# DrvPAPCNC.net
KiCad netlist of a schematic drawn in EAGLE
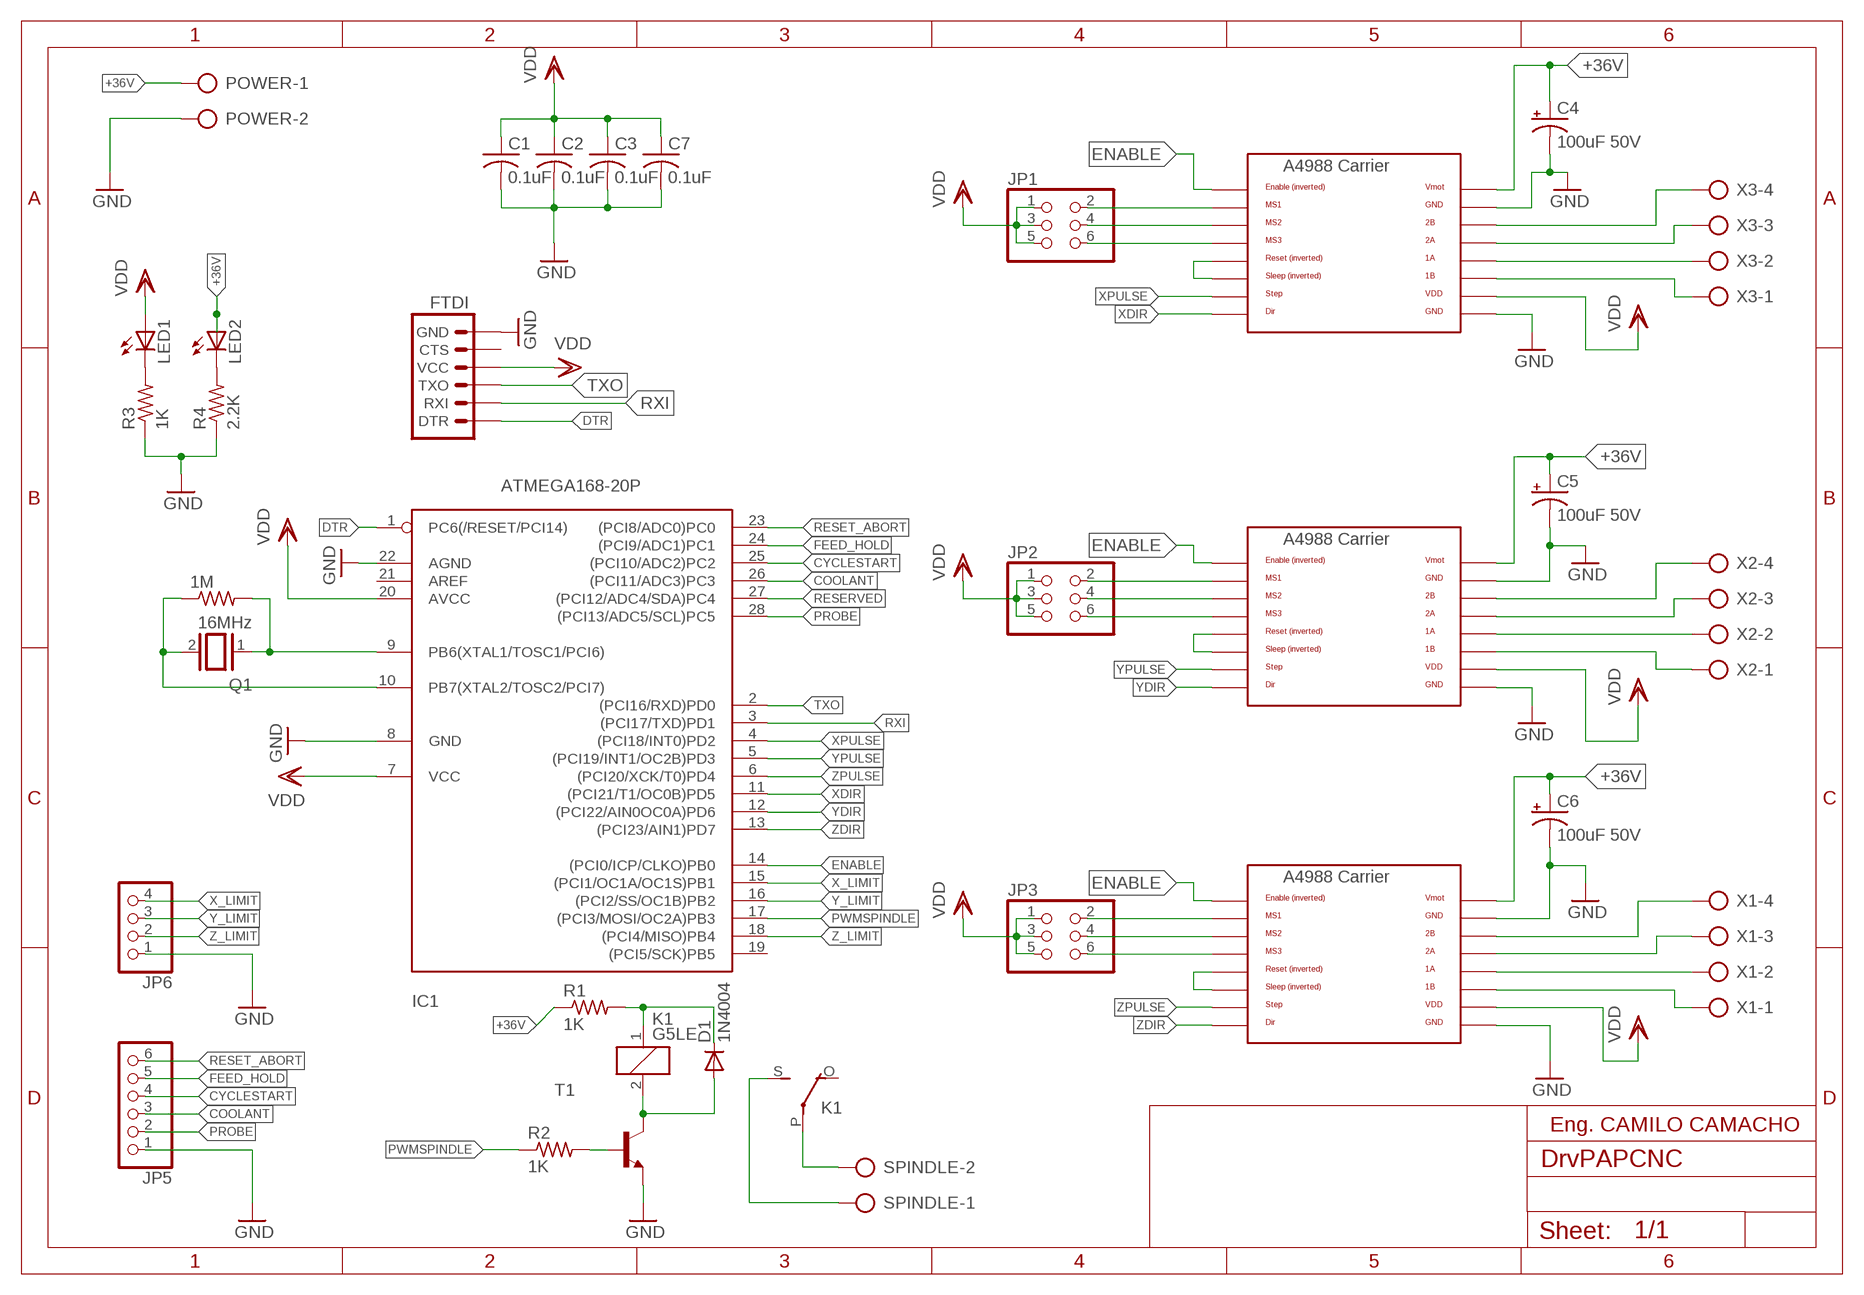
[diagram p0: schematic, sheet 1]

(export (version "E")
  (design (tool "Eeschema 10.0.6"))
  (components
    (comp (ref "1M")
      (value "R-US_0204/2V")
      (footprint "eagle-import:0204V")
      (libsource (lib "eagle-import") (part "R-US_0204/2V"))
    )
    (comp (ref "C1")
      (value "0.1uF")
      (footprint "eagle-import:C025-025X050")
      (libsource (lib "eagle-import") (part "C-US025-025X050"))
    )
    (comp (ref "C2")
      (value "0.1uF")
      (footprint "eagle-import:C025-025X050")
      (libsource (lib "eagle-import") (part "C-US025-025X050"))
    )
    (comp (ref "C3")
      (value "0.1uF")
      (footprint "eagle-import:C025-025X050")
      (libsource (lib "eagle-import") (part "C-US025-025X050"))
    )
    (comp (ref "C4")
      (value "100uF 50V")
      (footprint "eagle-import:E7,5-16")
      (libsource (lib "eagle-import") (part "CPOL-USE7.5-16"))
    )
    (comp (ref "C5")
      (value "100uF 50V")
      (footprint "eagle-import:E7,5-16")
      (libsource (lib "eagle-import") (part "CPOL-USE7.5-16"))
    )
    (comp (ref "C6")
      (value "100uF 50V")
      (footprint "eagle-import:E7,5-16")
      (libsource (lib "eagle-import") (part "CPOL-USE7.5-16"))
    )
    (comp (ref "C7")
      (value "0.1uF")
      (footprint "eagle-import:C025-025X050")
      (libsource (lib "eagle-import") (part "C-US025-025X050"))
    )
    (comp (ref "D1")
      (value "1N4004")
      (footprint "eagle-import:DO41-10")
      (libsource (lib "eagle-import") (part "1N4004"))
    )
    (comp (ref "FTDI")
      (value "ARDUINO_SERIAL_PROGRAMPTH")
      (footprint "eagle-import:1X06")
      (libsource (lib "eagle-import") (part "ARDUINO_SERIAL_PROGRAMPTH"))
    )
    (comp (ref "IC1")
      (value "ATMEGA168-20P")
      (footprint "eagle-import:DIL28-3")
      (libsource (lib "eagle-import") (part "ATMEGA168P-20"))
    )
    (comp (ref "JP1")
      (value "PINHD-2X3")
      (footprint "eagle-import:2X03")
      (libsource (lib "eagle-import") (part "PINHD-2X3"))
    )
    (comp (ref "JP2")
      (value "PINHD-2X3")
      (footprint "eagle-import:2X03")
      (libsource (lib "eagle-import") (part "PINHD-2X3"))
    )
    (comp (ref "JP3")
      (value "PINHD-2X3")
      (footprint "eagle-import:2X03")
      (libsource (lib "eagle-import") (part "PINHD-2X3"))
    )
    (comp (ref "JP5")
      (value "PINHD-1X6")
      (footprint "eagle-import:1X06")
      (libsource (lib "eagle-import") (part "PINHD-1X6"))
    )
    (comp (ref "JP6")
      (value "PINHD-1X4")
      (footprint "eagle-import:1X04")
      (libsource (lib "eagle-import") (part "PINHD-1X4"))
    )
    (comp (ref "K1")
      (value "G5LE")
      (footprint "eagle-import:G5LE")
      (libsource (lib "eagle-import") (part "G5LE"))
    )
    (comp (ref "LED1")
      (value "LED5MM")
      (footprint "eagle-import:LED5MM")
      (libsource (lib "eagle-import") (part "LED5MM"))
    )
    (comp (ref "LED2")
      (value "LED5MM")
      (footprint "eagle-import:LED5MM")
      (libsource (lib "eagle-import") (part "LED5MM"))
    )
    (comp (ref "POWER")
      (value "AK300/2")
      (footprint "eagle-import:AK300_2")
      (libsource (lib "eagle-import") (part "AK300/2"))
    )
    (comp (ref "Q1")
      (value "16MHz")
      (footprint "eagle-import:QS")
      (libsource (lib "eagle-import") (part "XTAL/S"))
    )
    (comp (ref "R1")
      (value "1K")
      (footprint "eagle-import:0207_10")
      (libsource (lib "eagle-import") (part "R-US_0207/10"))
    )
    (comp (ref "R2")
      (value "1K")
      (footprint "eagle-import:0207_10")
      (libsource (lib "eagle-import") (part "R-US_0207/10"))
    )
    (comp (ref "R3")
      (value "1K")
      (footprint "eagle-import:0207_10")
      (libsource (lib "eagle-import") (part "R-US_0207/10"))
    )
    (comp (ref "R4")
      (value "2.2K")
      (footprint "eagle-import:0207_10")
      (libsource (lib "eagle-import") (part "R-US_0207/10"))
    )
    (comp (ref "SPINDLE")
      (value "AK300/2")
      (footprint "eagle-import:AK300_2")
      (libsource (lib "eagle-import") (part "AK300/2"))
    )
    (comp (ref "T1")
      (value "2N3904-NPN-TO92-EBC")
      (footprint "eagle-import:TO92-EBC")
      (libsource (lib "eagle-import") (part "-NPN-TO92-EBC2N3904"))
    )
    (comp (ref "U$1")
      (value "A4988BREAKOUT")
      (footprint "eagle-import:A4988BREAKOUT")
      (libsource (lib "eagle-import") (part "A4988BREAKOUT"))
    )
    (comp (ref "U$2")
      (value "A4988BREAKOUT")
      (footprint "eagle-import:A4988BREAKOUT")
      (libsource (lib "eagle-import") (part "A4988BREAKOUT"))
    )
    (comp (ref "U$3")
      (value "A4988BREAKOUT")
      (footprint "eagle-import:A4988BREAKOUT")
      (libsource (lib "eagle-import") (part "A4988BREAKOUT"))
    )
    (comp (ref "X1")
      (value "AK300/4")
      (footprint "eagle-import:AK300_4")
      (libsource (lib "eagle-import") (part "AK300/4"))
    )
    (comp (ref "X2")
      (value "AK300/4")
      (footprint "eagle-import:AK300_4")
      (libsource (lib "eagle-import") (part "AK300/4"))
    )
    (comp (ref "X3")
      (value "AK300/4")
      (footprint "eagle-import:AK300_4")
      (libsource (lib "eagle-import") (part "AK300/4"))
    )
  )
  (nets
    (net (code "1") (name "+36V") (class "Default")
      (node (ref "C4") (pin "+") (pinfunction "+_+") (pintype "passive"))
      (node (ref "C5") (pin "+") (pinfunction "+_+") (pintype "passive"))
      (node (ref "C6") (pin "+") (pinfunction "+_+") (pintype "passive"))
      (node (ref "LED2") (pin "A") (pinfunction "A_A") (pintype "passive"))
      (node (ref "POWER") (pin "1") (pinfunction "KL_1") (pintype "passive"))
      (node (ref "R1") (pin "1") (pinfunction "1_1") (pintype "passive"))
      (node (ref "U$1") (pin "VMOT") (pinfunction "VMOT_VMOT") (pintype "power_in"))
      (node (ref "U$2") (pin "VMOT") (pinfunction "VMOT_VMOT") (pintype "power_in"))
      (node (ref "U$3") (pin "VMOT") (pinfunction "VMOT_VMOT") (pintype "power_in"))
    )
    (net (code "2") (name "COOLANT") (class "Default")
      (node (ref "IC1") (pin "26") (pinfunction "(PCI11/ADC3)PC3_26") (pintype "bidirectional"))
      (node (ref "JP5") (pin "3") (pinfunction "3_3") (pintype "passive"))
    )
    (net (code "3") (name "CYCLESTART") (class "Default")
      (node (ref "IC1") (pin "25") (pinfunction "(PCI10/ADC2)PC2_25") (pintype "bidirectional"))
      (node (ref "JP5") (pin "4") (pinfunction "4_4") (pintype "passive"))
    )
    (net (code "4") (name "DTR") (class "Default")
      (node (ref "FTDI") (pin "1") (pinfunction "DTR_1") (pintype "passive"))
      (node (ref "IC1") (pin "1") (pinfunction "PC6(/RESET/PCI14)_1") (pintype "bidirectional"))
    )
    (net (code "5") (name "ENABLE") (class "Default")
      (node (ref "IC1") (pin "14") (pinfunction "(PCI0/ICP/CLKO)PB0_14") (pintype "bidirectional"))
      (node (ref "U$1") (pin "EN") (pinfunction "EN_EN") (pintype "input"))
      (node (ref "U$2") (pin "EN") (pinfunction "EN_EN") (pintype "input"))
      (node (ref "U$3") (pin "EN") (pinfunction "EN_EN") (pintype "input"))
    )
    (net (code "6") (name "FEED_HOLD") (class "Default")
      (node (ref "IC1") (pin "24") (pinfunction "(PCI9/ADC1)PC1_24") (pintype "bidirectional"))
      (node (ref "JP5") (pin "5") (pinfunction "5_5") (pintype "passive"))
    )
    (net (code "7") (name "GND") (class "Default")
      (node (ref "C1") (pin "2") (pinfunction "2_2") (pintype "passive"))
      (node (ref "C2") (pin "2") (pinfunction "2_2") (pintype "passive"))
      (node (ref "C3") (pin "2") (pinfunction "2_2") (pintype "passive"))
      (node (ref "C4") (pin "-") (pinfunction "-_-") (pintype "passive"))
      (node (ref "C5") (pin "-") (pinfunction "-_-") (pintype "passive"))
      (node (ref "C6") (pin "-") (pinfunction "-_-") (pintype "passive"))
      (node (ref "C7") (pin "2") (pinfunction "2_2") (pintype "passive"))
      (node (ref "FTDI") (pin "6") (pinfunction "GND_6") (pintype "passive"))
      (node (ref "IC1") (pin "22") (pinfunction "AGND_22") (pintype "bidirectional"))
      (node (ref "IC1") (pin "8") (pinfunction "GND_8") (pintype "bidirectional"))
      (node (ref "JP5") (pin "1") (pinfunction "1_1") (pintype "passive"))
      (node (ref "JP6") (pin "1") (pinfunction "1_1") (pintype "passive"))
      (node (ref "POWER") (pin "2") (pinfunction "KL_2") (pintype "passive"))
      (node (ref "R3") (pin "1") (pinfunction "1_1") (pintype "passive"))
      (node (ref "R4") (pin "1") (pinfunction "1_1") (pintype "passive"))
      (node (ref "T1") (pin "E") (pinfunction "E_E") (pintype "passive"))
      (node (ref "U$1") (pin "GND") (pinfunction "GND_GND") (pintype "power_in"))
      (node (ref "U$1") (pin "GND@0") (pinfunction "GND_GND@0") (pintype "power_in"))
      (node (ref "U$2") (pin "GND") (pinfunction "GND_GND") (pintype "power_in"))
      (node (ref "U$2") (pin "GND@0") (pinfunction "GND_GND@0") (pintype "power_in"))
      (node (ref "U$3") (pin "GND") (pinfunction "GND_GND") (pintype "power_in"))
      (node (ref "U$3") (pin "GND@0") (pinfunction "GND_GND@0") (pintype "power_in"))
    )
    (net (code "8") (name "Net-(D1-PadA)") (class "Default")
      (node (ref "D1") (pin "A") (pinfunction "A_A") (pintype "passive"))
      (node (ref "K1") (pin "2") (pinfunction "2_2") (pintype "passive"))
      (node (ref "T1") (pin "C") (pinfunction "C_C") (pintype "passive"))
    )
    (net (code "9") (name "Net-(D1-PadC)") (class "Default")
      (node (ref "D1") (pin "C") (pinfunction "C_C") (pintype "passive"))
      (node (ref "K1") (pin "1") (pinfunction "1_1") (pintype "passive"))
      (node (ref "R1") (pin "2") (pinfunction "2_2") (pintype "passive"))
    )
    (net (code "10") (name "Net-(IC1-PB6(XTAL1{slash}TOSC1{slash}PCI6))") (class "Default")
      (node (ref "1M") (pin "2") (pinfunction "2_2") (pintype "passive"))
      (node (ref "IC1") (pin "9") (pinfunction "PB6(XTAL1/TOSC1/PCI6)_9") (pintype "bidirectional"))
      (node (ref "Q1") (pin "1") (pinfunction "1_1") (pintype "passive"))
    )
    (net (code "11") (name "Net-(IC1-PB7(XTAL2{slash}TOSC2{slash}PCI7))") (class "Default")
      (node (ref "1M") (pin "1") (pinfunction "1_1") (pintype "passive"))
      (node (ref "IC1") (pin "10") (pinfunction "PB7(XTAL2/TOSC2/PCI7)_10") (pintype "bidirectional"))
      (node (ref "Q1") (pin "2") (pinfunction "2_2") (pintype "passive"))
    )
    (net (code "12") (name "Net-(JP1-Pad2)") (class "Default")
      (node (ref "JP1") (pin "2") (pinfunction "2_2") (pintype "passive"))
      (node (ref "U$1") (pin "MS1") (pinfunction "MS1_MS1") (pintype "input"))
    )
    (net (code "13") (name "Net-(JP1-Pad4)") (class "Default")
      (node (ref "JP1") (pin "4") (pinfunction "4_4") (pintype "passive"))
      (node (ref "U$1") (pin "MS2") (pinfunction "MS2_MS2") (pintype "input"))
    )
    (net (code "14") (name "Net-(JP1-Pad6)") (class "Default")
      (node (ref "JP1") (pin "6") (pinfunction "6_6") (pintype "passive"))
      (node (ref "U$1") (pin "MS3") (pinfunction "MS3_MS3") (pintype "input"))
    )
    (net (code "15") (name "Net-(JP2-Pad2)") (class "Default")
      (node (ref "JP2") (pin "2") (pinfunction "2_2") (pintype "passive"))
      (node (ref "U$2") (pin "MS1") (pinfunction "MS1_MS1") (pintype "input"))
    )
    (net (code "16") (name "Net-(JP2-Pad4)") (class "Default")
      (node (ref "JP2") (pin "4") (pinfunction "4_4") (pintype "passive"))
      (node (ref "U$2") (pin "MS2") (pinfunction "MS2_MS2") (pintype "input"))
    )
    (net (code "17") (name "Net-(JP2-Pad6)") (class "Default")
      (node (ref "JP2") (pin "6") (pinfunction "6_6") (pintype "passive"))
      (node (ref "U$2") (pin "MS3") (pinfunction "MS3_MS3") (pintype "input"))
    )
    (net (code "18") (name "Net-(JP3-Pad2)") (class "Default")
      (node (ref "JP3") (pin "2") (pinfunction "2_2") (pintype "passive"))
      (node (ref "U$3") (pin "MS1") (pinfunction "MS1_MS1") (pintype "input"))
    )
    (net (code "19") (name "Net-(JP3-Pad4)") (class "Default")
      (node (ref "JP3") (pin "4") (pinfunction "4_4") (pintype "passive"))
      (node (ref "U$3") (pin "MS2") (pinfunction "MS2_MS2") (pintype "input"))
    )
    (net (code "20") (name "Net-(JP3-Pad6)") (class "Default")
      (node (ref "JP3") (pin "6") (pinfunction "6_6") (pintype "passive"))
      (node (ref "U$3") (pin "MS3") (pinfunction "MS3_MS3") (pintype "input"))
    )
    (net (code "21") (name "Net-(LED1-C)") (class "Default")
      (node (ref "LED1") (pin "K") (pinfunction "C_K") (pintype "passive"))
      (node (ref "R3") (pin "2") (pinfunction "2_2") (pintype "passive"))
    )
    (net (code "22") (name "Net-(LED2-C)") (class "Default")
      (node (ref "LED2") (pin "K") (pinfunction "C_K") (pintype "passive"))
      (node (ref "R4") (pin "2") (pinfunction "2_2") (pintype "passive"))
    )
    (net (code "23") (name "Net-(R2-Pad2)") (class "Default")
      (node (ref "R2") (pin "2") (pinfunction "2_2") (pintype "passive"))
      (node (ref "T1") (pin "B") (pinfunction "B_B") (pintype "passive"))
    )
    (net (code "24") (name "Net-(SPINDLEA-KL)") (class "Default")
      (node (ref "K1") (pin "S") (pinfunction "S_S") (pintype "passive"))
      (node (ref "SPINDLE") (pin "1") (pinfunction "KL_1") (pintype "passive"))
    )
    (net (code "25") (name "Net-(SPINDLEB-KL)") (class "Default")
      (node (ref "K1") (pin "P") (pinfunction "P_P") (pintype "passive"))
      (node (ref "SPINDLE") (pin "2") (pinfunction "KL_2") (pintype "passive"))
    )
    (net (code "26") (name "Net-(U$1-SLEEP)") (class "Default")
      (node (ref "U$1") (pin "RST") (pinfunction "RST_RST") (pintype "input"))
      (node (ref "U$1") (pin "SLP") (pinfunction "SLEEP_SLP") (pintype "input"))
    )
    (net (code "27") (name "Net-(U$2-SLEEP)") (class "Default")
      (node (ref "U$2") (pin "RST") (pinfunction "RST_RST") (pintype "input"))
      (node (ref "U$2") (pin "SLP") (pinfunction "SLEEP_SLP") (pintype "input"))
    )
    (net (code "28") (name "Net-(U$3-SLEEP)") (class "Default")
      (node (ref "U$3") (pin "RST") (pinfunction "RST_RST") (pintype "input"))
      (node (ref "U$3") (pin "SLP") (pinfunction "SLEEP_SLP") (pintype "input"))
    )
    (net (code "29") (name "Net-(X1A-KL)") (class "Default")
      (node (ref "U$3") (pin "1B") (pinfunction "1B_1B") (pintype "output"))
      (node (ref "X1") (pin "1") (pinfunction "KL_1") (pintype "passive"))
    )
    (net (code "30") (name "Net-(X1B-KL)") (class "Default")
      (node (ref "U$3") (pin "1A") (pinfunction "1A_1A") (pintype "output"))
      (node (ref "X1") (pin "2") (pinfunction "KL_2") (pintype "passive"))
    )
    (net (code "31") (name "Net-(X1C-KL)") (class "Default")
      (node (ref "U$3") (pin "2A") (pinfunction "2A_2A") (pintype "output"))
      (node (ref "X1") (pin "3") (pinfunction "KL_3") (pintype "passive"))
    )
    (net (code "32") (name "Net-(X1D-KL)") (class "Default")
      (node (ref "U$3") (pin "2B") (pinfunction "2B_2B") (pintype "output"))
      (node (ref "X1") (pin "4") (pinfunction "KL_4") (pintype "passive"))
    )
    (net (code "33") (name "Net-(X2A-KL)") (class "Default")
      (node (ref "U$2") (pin "1B") (pinfunction "1B_1B") (pintype "output"))
      (node (ref "X2") (pin "1") (pinfunction "KL_1") (pintype "passive"))
    )
    (net (code "34") (name "Net-(X2B-KL)") (class "Default")
      (node (ref "U$2") (pin "1A") (pinfunction "1A_1A") (pintype "output"))
      (node (ref "X2") (pin "2") (pinfunction "KL_2") (pintype "passive"))
    )
    (net (code "35") (name "Net-(X2C-KL)") (class "Default")
      (node (ref "U$2") (pin "2A") (pinfunction "2A_2A") (pintype "output"))
      (node (ref "X2") (pin "3") (pinfunction "KL_3") (pintype "passive"))
    )
    (net (code "36") (name "Net-(X2D-KL)") (class "Default")
      (node (ref "U$2") (pin "2B") (pinfunction "2B_2B") (pintype "output"))
      (node (ref "X2") (pin "4") (pinfunction "KL_4") (pintype "passive"))
    )
    (net (code "37") (name "Net-(X3A-KL)") (class "Default")
      (node (ref "U$1") (pin "1B") (pinfunction "1B_1B") (pintype "output"))
      (node (ref "X3") (pin "1") (pinfunction "KL_1") (pintype "passive"))
    )
    (net (code "38") (name "Net-(X3B-KL)") (class "Default")
      (node (ref "U$1") (pin "1A") (pinfunction "1A_1A") (pintype "output"))
      (node (ref "X3") (pin "2") (pinfunction "KL_2") (pintype "passive"))
    )
    (net (code "39") (name "Net-(X3C-KL)") (class "Default")
      (node (ref "U$1") (pin "2A") (pinfunction "2A_2A") (pintype "output"))
      (node (ref "X3") (pin "3") (pinfunction "KL_3") (pintype "passive"))
    )
    (net (code "40") (name "Net-(X3D-KL)") (class "Default")
      (node (ref "U$1") (pin "2B") (pinfunction "2B_2B") (pintype "output"))
      (node (ref "X3") (pin "4") (pinfunction "KL_4") (pintype "passive"))
    )
    (net (code "41") (name "PROBE") (class "Default")
      (node (ref "IC1") (pin "28") (pinfunction "(PCI13/ADC5/SCL)PC5_28") (pintype "bidirectional"))
      (node (ref "JP5") (pin "2") (pinfunction "2_2") (pintype "passive"))
    )
    (net (code "42") (name "PWMSPINDLE") (class "Default")
      (node (ref "IC1") (pin "17") (pinfunction "(PCI3/MOSI/OC2A)PB3_17") (pintype "bidirectional"))
      (node (ref "R2") (pin "1") (pinfunction "1_1") (pintype "passive"))
    )
    (net (code "43") (name "RESERVED") (class "Default")
      (node (ref "IC1") (pin "27") (pinfunction "(PCI12/ADC4/SDA)PC4_27") (pintype "bidirectional"))
    )
    (net (code "44") (name "RESET_ABORT") (class "Default")
      (node (ref "IC1") (pin "23") (pinfunction "(PCI8/ADC0)PC0_23") (pintype "bidirectional"))
      (node (ref "JP5") (pin "6") (pinfunction "6_6") (pintype "passive"))
    )
    (net (code "45") (name "RXI") (class "Default")
      (node (ref "FTDI") (pin "2") (pinfunction "RXI_2") (pintype "passive"))
      (node (ref "IC1") (pin "3") (pinfunction "(PCI17/TXD)PD1_3") (pintype "bidirectional"))
    )
    (net (code "46") (name "TXO") (class "Default")
      (node (ref "FTDI") (pin "3") (pinfunction "TXO_3") (pintype "passive"))
      (node (ref "IC1") (pin "2") (pinfunction "(PCI16/RXD)PD0_2") (pintype "bidirectional"))
    )
    (net (code "47") (name "VDD") (class "Default")
      (node (ref "C1") (pin "1") (pinfunction "1_1") (pintype "passive"))
      (node (ref "C2") (pin "1") (pinfunction "1_1") (pintype "passive"))
      (node (ref "C3") (pin "1") (pinfunction "1_1") (pintype "passive"))
      (node (ref "C7") (pin "1") (pinfunction "1_1") (pintype "passive"))
      (node (ref "FTDI") (pin "4") (pinfunction "VCC_4") (pintype "passive"))
      (node (ref "IC1") (pin "20") (pinfunction "AVCC_20") (pintype "bidirectional"))
      (node (ref "IC1") (pin "7") (pinfunction "VCC_7") (pintype "bidirectional"))
      (node (ref "JP1") (pin "1") (pinfunction "1_1") (pintype "passive"))
      (node (ref "JP1") (pin "3") (pinfunction "3_3") (pintype "passive"))
      (node (ref "JP1") (pin "5") (pinfunction "5_5") (pintype "passive"))
      (node (ref "JP2") (pin "1") (pinfunction "1_1") (pintype "passive"))
      (node (ref "JP2") (pin "3") (pinfunction "3_3") (pintype "passive"))
      (node (ref "JP2") (pin "5") (pinfunction "5_5") (pintype "passive"))
      (node (ref "JP3") (pin "1") (pinfunction "1_1") (pintype "passive"))
      (node (ref "JP3") (pin "3") (pinfunction "3_3") (pintype "passive"))
      (node (ref "JP3") (pin "5") (pinfunction "5_5") (pintype "passive"))
      (node (ref "LED1") (pin "A") (pinfunction "A_A") (pintype "passive"))
      (node (ref "U$1") (pin "VDD") (pinfunction "VDD_VDD") (pintype "power_in"))
      (node (ref "U$2") (pin "VDD") (pinfunction "VDD_VDD") (pintype "power_in"))
      (node (ref "U$3") (pin "VDD") (pinfunction "VDD_VDD") (pintype "power_in"))
    )
    (net (code "48") (name "XDIR") (class "Default")
      (node (ref "IC1") (pin "11") (pinfunction "(PCI21/T1/OC0B)PD5_11") (pintype "bidirectional"))
      (node (ref "U$1") (pin "DIR") (pinfunction "DIR_DIR") (pintype "input"))
    )
    (net (code "49") (name "XPULSE") (class "Default")
      (node (ref "IC1") (pin "4") (pinfunction "(PCI18/INT0)PD2_4") (pintype "bidirectional"))
      (node (ref "U$1") (pin "STEP") (pinfunction "STEP_STEP") (pintype "input"))
    )
    (net (code "50") (name "X_LIMIT") (class "Default")
      (node (ref "IC1") (pin "15") (pinfunction "(PCI1/OC1A/OC1S)PB1_15") (pintype "bidirectional"))
      (node (ref "JP6") (pin "4") (pinfunction "4_4") (pintype "passive"))
    )
    (net (code "51") (name "YDIR") (class "Default")
      (node (ref "IC1") (pin "12") (pinfunction "(PCI22/AIN0OC0A)PD6_12") (pintype "bidirectional"))
      (node (ref "U$2") (pin "DIR") (pinfunction "DIR_DIR") (pintype "input"))
    )
    (net (code "52") (name "YPULSE") (class "Default")
      (node (ref "IC1") (pin "5") (pinfunction "(PCI19/INT1/OC2B)PD3_5") (pintype "bidirectional"))
      (node (ref "U$2") (pin "STEP") (pinfunction "STEP_STEP") (pintype "input"))
    )
    (net (code "53") (name "Y_LIMIT") (class "Default")
      (node (ref "IC1") (pin "16") (pinfunction "(PCI2/SS/OC1B)PB2_16") (pintype "bidirectional"))
      (node (ref "JP6") (pin "3") (pinfunction "3_3") (pintype "passive"))
    )
    (net (code "54") (name "ZDIR") (class "Default")
      (node (ref "IC1") (pin "13") (pinfunction "(PCI23/AIN1)PD7_13") (pintype "bidirectional"))
      (node (ref "U$3") (pin "DIR") (pinfunction "DIR_DIR") (pintype "input"))
    )
    (net (code "55") (name "ZPULSE") (class "Default")
      (node (ref "IC1") (pin "6") (pinfunction "(PCI20/XCK/T0)PD4_6") (pintype "bidirectional"))
      (node (ref "U$3") (pin "STEP") (pinfunction "STEP_STEP") (pintype "input"))
    )
    (net (code "56") (name "Z_LIMIT") (class "Default")
      (node (ref "IC1") (pin "18") (pinfunction "(PCI4/MISO)PB4_18") (pintype "bidirectional"))
      (node (ref "JP6") (pin "2") (pinfunction "2_2") (pintype "passive"))
    )
    (net (code "57") (name "unconnected-(FTDI-CTS-Pad5)") (class "Default")
      (node (ref "FTDI") (pin "5") (pinfunction "CTS_5") (pintype "passive"))
    )
    (net (code "58") (name "unconnected-(IC1-(PCI5{slash}SCK)PB5-Pad19)") (class "Default")
      (node (ref "IC1") (pin "19") (pinfunction "(PCI5/SCK)PB5_19") (pintype "bidirectional"))
    )
    (net (code "59") (name "unconnected-(IC1-AREF-Pad21)") (class "Default")
      (node (ref "IC1") (pin "21") (pinfunction "AREF_21") (pintype "bidirectional"))
    )
    (net (code "60") (name "unconnected-(K1-PadO)") (class "Default")
      (node (ref "K1") (pin "O") (pinfunction "O_O") (pintype "passive"))
    )
  )
)
